# LED_Matrix.net
KiCad netlist of a schematic drawn in Altium Designer
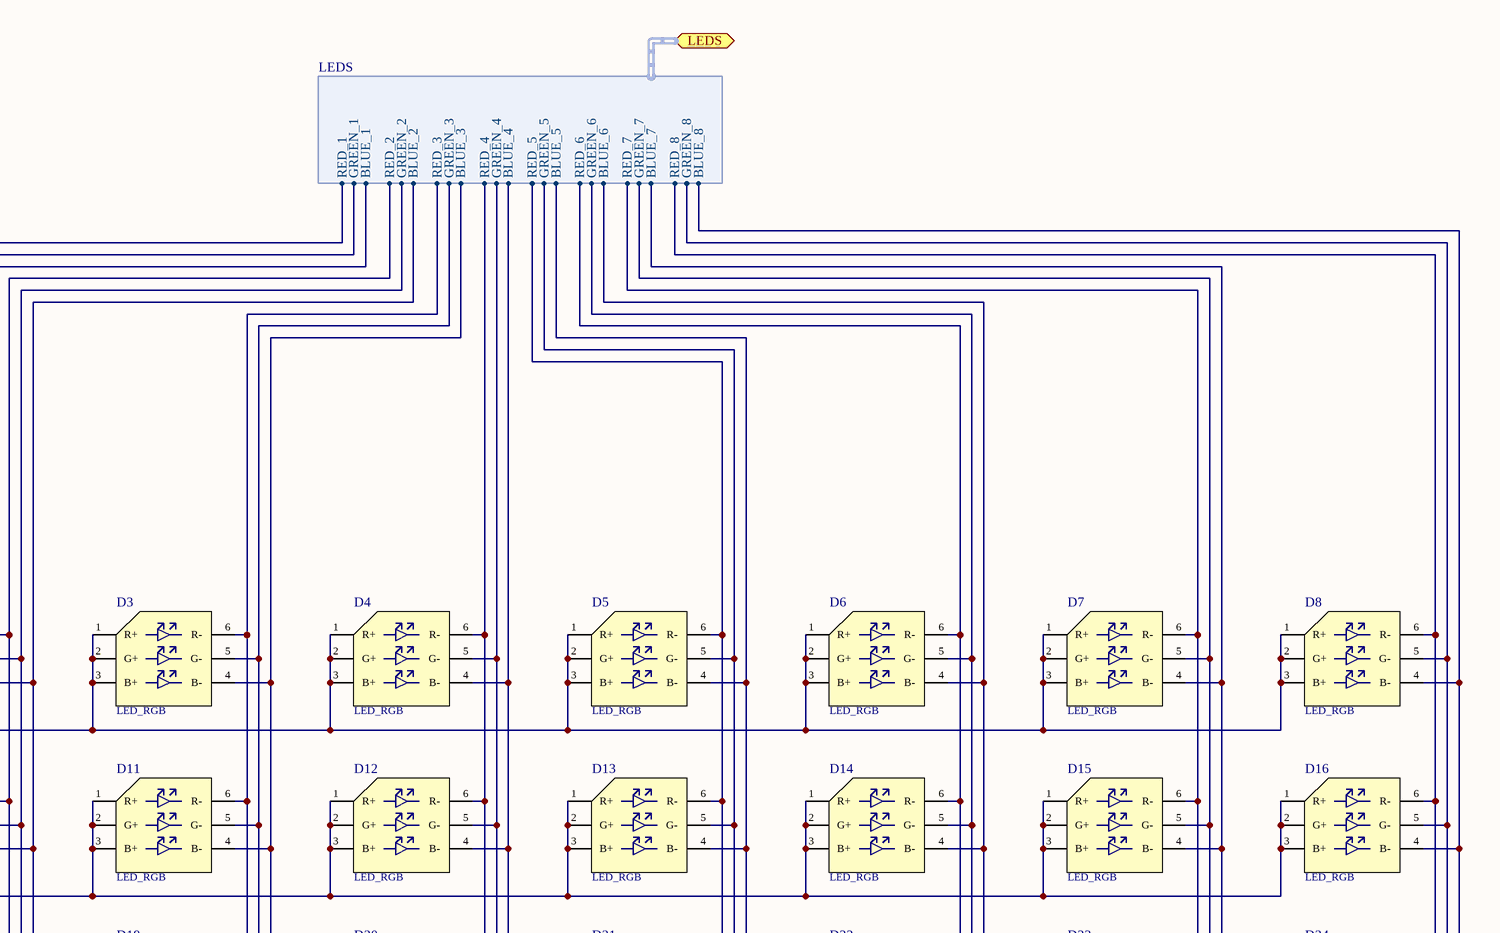
[diagram p0: LED Matrix.SchDoc, top right]
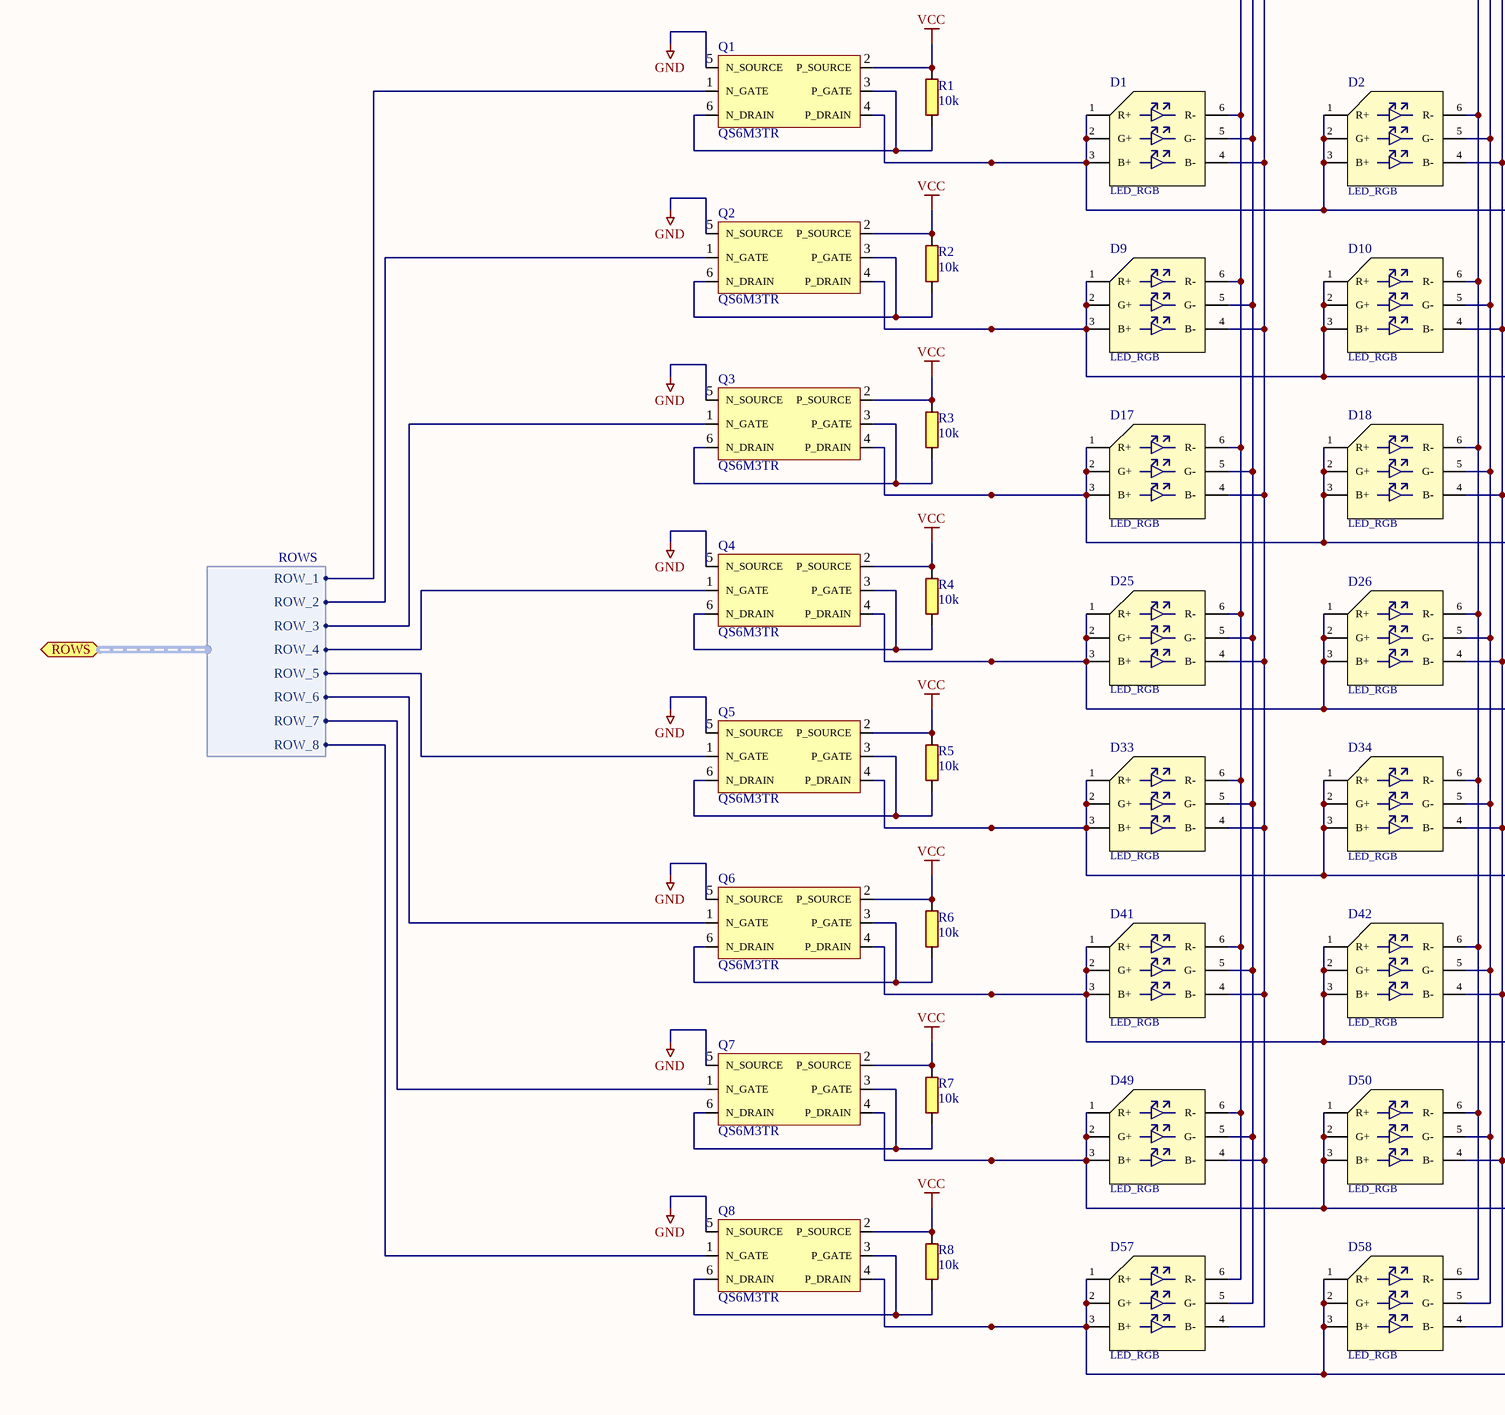
[diagram p1: LED Matrix.SchDoc, bottom left]
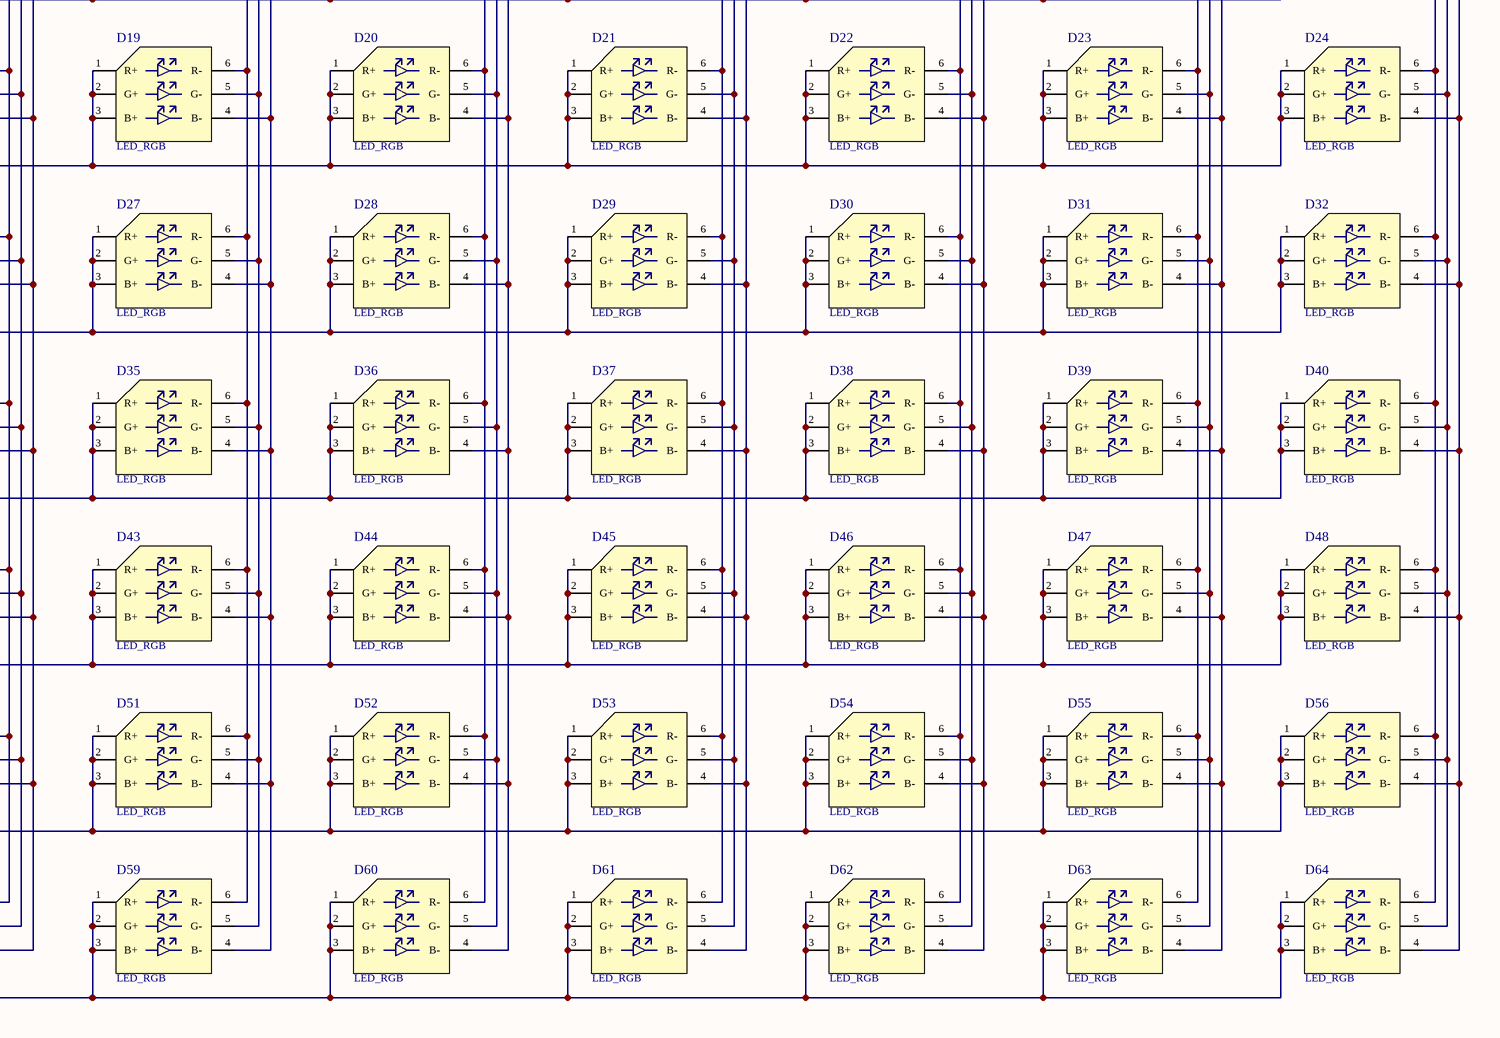
[diagram p2: LED Matrix.SchDoc, bottom right]

(export (version "E")
  (design (tool "Eeschema 10.0.6"))
  (components
    (comp (ref "D1")
      (value "LED_RGB")
      (footprint "LED5050_RGB_N")
      (description "LED RGB, independent colors")
      (libsource (lib "OVLib") (part "LED_RGB_IND_CHIP"))
    )
    (comp (ref "D2")
      (value "LED_RGB")
      (footprint "LED5050_RGB_N")
      (description "LED RGB, independent colors")
      (libsource (lib "OVLib") (part "LED_RGB_IND_CHIP"))
    )
    (comp (ref "D3")
      (value "LED_RGB")
      (footprint "LED5050_RGB_N")
      (description "LED RGB, independent colors")
      (libsource (lib "OVLib") (part "LED_RGB_IND_CHIP"))
    )
    (comp (ref "D4")
      (value "LED_RGB")
      (footprint "LED5050_RGB_N")
      (description "LED RGB, independent colors")
      (libsource (lib "OVLib") (part "LED_RGB_IND_CHIP"))
    )
    (comp (ref "D5")
      (value "LED_RGB")
      (footprint "LED5050_RGB_N")
      (description "LED RGB, independent colors")
      (libsource (lib "OVLib") (part "LED_RGB_IND_CHIP"))
    )
    (comp (ref "D6")
      (value "LED_RGB")
      (footprint "LED5050_RGB_N")
      (description "LED RGB, independent colors")
      (libsource (lib "OVLib") (part "LED_RGB_IND_CHIP"))
    )
    (comp (ref "D7")
      (value "LED_RGB")
      (footprint "LED5050_RGB_N")
      (description "LED RGB, independent colors")
      (libsource (lib "OVLib") (part "LED_RGB_IND_CHIP"))
    )
    (comp (ref "D8")
      (value "LED_RGB")
      (footprint "LED5050_RGB_N")
      (description "LED RGB, independent colors")
      (libsource (lib "OVLib") (part "LED_RGB_IND_CHIP"))
    )
    (comp (ref "D9")
      (value "LED_RGB")
      (footprint "LED5050_RGB_N")
      (description "LED RGB, independent colors")
      (libsource (lib "OVLib") (part "LED_RGB_IND_CHIP"))
    )
    (comp (ref "D10")
      (value "LED_RGB")
      (footprint "LED5050_RGB_N")
      (description "LED RGB, independent colors")
      (libsource (lib "OVLib") (part "LED_RGB_IND_CHIP"))
    )
    (comp (ref "D11")
      (value "LED_RGB")
      (footprint "LED5050_RGB_N")
      (description "LED RGB, independent colors")
      (libsource (lib "OVLib") (part "LED_RGB_IND_CHIP"))
    )
    (comp (ref "D12")
      (value "LED_RGB")
      (footprint "LED5050_RGB_N")
      (description "LED RGB, independent colors")
      (libsource (lib "OVLib") (part "LED_RGB_IND_CHIP"))
    )
    (comp (ref "D13")
      (value "LED_RGB")
      (footprint "LED5050_RGB_N")
      (description "LED RGB, independent colors")
      (libsource (lib "OVLib") (part "LED_RGB_IND_CHIP"))
    )
    (comp (ref "D14")
      (value "LED_RGB")
      (footprint "LED5050_RGB_N")
      (description "LED RGB, independent colors")
      (libsource (lib "OVLib") (part "LED_RGB_IND_CHIP"))
    )
    (comp (ref "D15")
      (value "LED_RGB")
      (footprint "LED5050_RGB_N")
      (description "LED RGB, independent colors")
      (libsource (lib "OVLib") (part "LED_RGB_IND_CHIP"))
    )
    (comp (ref "D16")
      (value "LED_RGB")
      (footprint "LED5050_RGB_N")
      (description "LED RGB, independent colors")
      (libsource (lib "OVLib") (part "LED_RGB_IND_CHIP"))
    )
    (comp (ref "D17")
      (value "LED_RGB")
      (footprint "LED5050_RGB_N")
      (description "LED RGB, independent colors")
      (libsource (lib "OVLib") (part "LED_RGB_IND_CHIP"))
    )
    (comp (ref "D18")
      (value "LED_RGB")
      (footprint "LED5050_RGB_N")
      (description "LED RGB, independent colors")
      (libsource (lib "OVLib") (part "LED_RGB_IND_CHIP"))
    )
    (comp (ref "D19")
      (value "LED_RGB")
      (footprint "LED5050_RGB_N")
      (description "LED RGB, independent colors")
      (libsource (lib "OVLib") (part "LED_RGB_IND_CHIP"))
    )
    (comp (ref "D20")
      (value "LED_RGB")
      (footprint "LED5050_RGB_N")
      (description "LED RGB, independent colors")
      (libsource (lib "OVLib") (part "LED_RGB_IND_CHIP"))
    )
    (comp (ref "D21")
      (value "LED_RGB")
      (footprint "LED5050_RGB_N")
      (description "LED RGB, independent colors")
      (libsource (lib "OVLib") (part "LED_RGB_IND_CHIP"))
    )
    (comp (ref "D22")
      (value "LED_RGB")
      (footprint "LED5050_RGB_N")
      (description "LED RGB, independent colors")
      (libsource (lib "OVLib") (part "LED_RGB_IND_CHIP"))
    )
    (comp (ref "D23")
      (value "LED_RGB")
      (footprint "LED5050_RGB_N")
      (description "LED RGB, independent colors")
      (libsource (lib "OVLib") (part "LED_RGB_IND_CHIP"))
    )
    (comp (ref "D24")
      (value "LED_RGB")
      (footprint "LED5050_RGB_N")
      (description "LED RGB, independent colors")
      (libsource (lib "OVLib") (part "LED_RGB_IND_CHIP"))
    )
    (comp (ref "D25")
      (value "LED_RGB")
      (footprint "LED5050_RGB_N")
      (description "LED RGB, independent colors")
      (libsource (lib "OVLib") (part "LED_RGB_IND_CHIP"))
    )
    (comp (ref "D26")
      (value "LED_RGB")
      (footprint "LED5050_RGB_N")
      (description "LED RGB, independent colors")
      (libsource (lib "OVLib") (part "LED_RGB_IND_CHIP"))
    )
    (comp (ref "D27")
      (value "LED_RGB")
      (footprint "LED5050_RGB_N")
      (description "LED RGB, independent colors")
      (libsource (lib "OVLib") (part "LED_RGB_IND_CHIP"))
    )
    (comp (ref "D28")
      (value "LED_RGB")
      (footprint "LED5050_RGB_N")
      (description "LED RGB, independent colors")
      (libsource (lib "OVLib") (part "LED_RGB_IND_CHIP"))
    )
    (comp (ref "D29")
      (value "LED_RGB")
      (footprint "LED5050_RGB_N")
      (description "LED RGB, independent colors")
      (libsource (lib "OVLib") (part "LED_RGB_IND_CHIP"))
    )
    (comp (ref "D30")
      (value "LED_RGB")
      (footprint "LED5050_RGB_N")
      (description "LED RGB, independent colors")
      (libsource (lib "OVLib") (part "LED_RGB_IND_CHIP"))
    )
    (comp (ref "D31")
      (value "LED_RGB")
      (footprint "LED5050_RGB_N")
      (description "LED RGB, independent colors")
      (libsource (lib "OVLib") (part "LED_RGB_IND_CHIP"))
    )
    (comp (ref "D32")
      (value "LED_RGB")
      (footprint "LED5050_RGB_N")
      (description "LED RGB, independent colors")
      (libsource (lib "OVLib") (part "LED_RGB_IND_CHIP"))
    )
    (comp (ref "D33")
      (value "LED_RGB")
      (footprint "LED5050_RGB_N")
      (description "LED RGB, independent colors")
      (libsource (lib "OVLib") (part "LED_RGB_IND_CHIP"))
    )
    (comp (ref "D34")
      (value "LED_RGB")
      (footprint "LED5050_RGB_N")
      (description "LED RGB, independent colors")
      (libsource (lib "OVLib") (part "LED_RGB_IND_CHIP"))
    )
    (comp (ref "D35")
      (value "LED_RGB")
      (footprint "LED5050_RGB_N")
      (description "LED RGB, independent colors")
      (libsource (lib "OVLib") (part "LED_RGB_IND_CHIP"))
    )
    (comp (ref "D36")
      (value "LED_RGB")
      (footprint "LED5050_RGB_N")
      (description "LED RGB, independent colors")
      (libsource (lib "OVLib") (part "LED_RGB_IND_CHIP"))
    )
    (comp (ref "D37")
      (value "LED_RGB")
      (footprint "LED5050_RGB_N")
      (description "LED RGB, independent colors")
      (libsource (lib "OVLib") (part "LED_RGB_IND_CHIP"))
    )
    (comp (ref "D38")
      (value "LED_RGB")
      (footprint "LED5050_RGB_N")
      (description "LED RGB, independent colors")
      (libsource (lib "OVLib") (part "LED_RGB_IND_CHIP"))
    )
    (comp (ref "D39")
      (value "LED_RGB")
      (footprint "LED5050_RGB_N")
      (description "LED RGB, independent colors")
      (libsource (lib "OVLib") (part "LED_RGB_IND_CHIP"))
    )
    (comp (ref "D40")
      (value "LED_RGB")
      (footprint "LED5050_RGB_N")
      (description "LED RGB, independent colors")
      (libsource (lib "OVLib") (part "LED_RGB_IND_CHIP"))
    )
    (comp (ref "D41")
      (value "LED_RGB")
      (footprint "LED5050_RGB_N")
      (description "LED RGB, independent colors")
      (libsource (lib "OVLib") (part "LED_RGB_IND_CHIP"))
    )
    (comp (ref "D42")
      (value "LED_RGB")
      (footprint "LED5050_RGB_N")
      (description "LED RGB, independent colors")
      (libsource (lib "OVLib") (part "LED_RGB_IND_CHIP"))
    )
    (comp (ref "D43")
      (value "LED_RGB")
      (footprint "LED5050_RGB_N")
      (description "LED RGB, independent colors")
      (libsource (lib "OVLib") (part "LED_RGB_IND_CHIP"))
    )
    (comp (ref "D44")
      (value "LED_RGB")
      (footprint "LED5050_RGB_N")
      (description "LED RGB, independent colors")
      (libsource (lib "OVLib") (part "LED_RGB_IND_CHIP"))
    )
    (comp (ref "D45")
      (value "LED_RGB")
      (footprint "LED5050_RGB_N")
      (description "LED RGB, independent colors")
      (libsource (lib "OVLib") (part "LED_RGB_IND_CHIP"))
    )
    (comp (ref "D46")
      (value "LED_RGB")
      (footprint "LED5050_RGB_N")
      (description "LED RGB, independent colors")
      (libsource (lib "OVLib") (part "LED_RGB_IND_CHIP"))
    )
    (comp (ref "D47")
      (value "LED_RGB")
      (footprint "LED5050_RGB_N")
      (description "LED RGB, independent colors")
      (libsource (lib "OVLib") (part "LED_RGB_IND_CHIP"))
    )
    (comp (ref "D48")
      (value "LED_RGB")
      (footprint "LED5050_RGB_N")
      (description "LED RGB, independent colors")
      (libsource (lib "OVLib") (part "LED_RGB_IND_CHIP"))
    )
    (comp (ref "D49")
      (value "LED_RGB")
      (footprint "LED5050_RGB_N")
      (description "LED RGB, independent colors")
      (libsource (lib "OVLib") (part "LED_RGB_IND_CHIP"))
    )
    (comp (ref "D50")
      (value "LED_RGB")
      (footprint "LED5050_RGB_N")
      (description "LED RGB, independent colors")
      (libsource (lib "OVLib") (part "LED_RGB_IND_CHIP"))
    )
    (comp (ref "D51")
      (value "LED_RGB")
      (footprint "LED5050_RGB_N")
      (description "LED RGB, independent colors")
      (libsource (lib "OVLib") (part "LED_RGB_IND_CHIP"))
    )
    (comp (ref "D52")
      (value "LED_RGB")
      (footprint "LED5050_RGB_N")
      (description "LED RGB, independent colors")
      (libsource (lib "OVLib") (part "LED_RGB_IND_CHIP"))
    )
    (comp (ref "D53")
      (value "LED_RGB")
      (footprint "LED5050_RGB_N")
      (description "LED RGB, independent colors")
      (libsource (lib "OVLib") (part "LED_RGB_IND_CHIP"))
    )
    (comp (ref "D54")
      (value "LED_RGB")
      (footprint "LED5050_RGB_N")
      (description "LED RGB, independent colors")
      (libsource (lib "OVLib") (part "LED_RGB_IND_CHIP"))
    )
    (comp (ref "D55")
      (value "LED_RGB")
      (footprint "LED5050_RGB_N")
      (description "LED RGB, independent colors")
      (libsource (lib "OVLib") (part "LED_RGB_IND_CHIP"))
    )
    (comp (ref "D56")
      (value "LED_RGB")
      (footprint "LED5050_RGB_N")
      (description "LED RGB, independent colors")
      (libsource (lib "OVLib") (part "LED_RGB_IND_CHIP"))
    )
    (comp (ref "D57")
      (value "LED_RGB")
      (footprint "LED5050_RGB_N")
      (description "LED RGB, independent colors")
      (libsource (lib "OVLib") (part "LED_RGB_IND_CHIP"))
    )
    (comp (ref "D58")
      (value "LED_RGB")
      (footprint "LED5050_RGB_N")
      (description "LED RGB, independent colors")
      (libsource (lib "OVLib") (part "LED_RGB_IND_CHIP"))
    )
    (comp (ref "D59")
      (value "LED_RGB")
      (footprint "LED5050_RGB_N")
      (description "LED RGB, independent colors")
      (libsource (lib "OVLib") (part "LED_RGB_IND_CHIP"))
    )
    (comp (ref "D60")
      (value "LED_RGB")
      (footprint "LED5050_RGB_N")
      (description "LED RGB, independent colors")
      (libsource (lib "OVLib") (part "LED_RGB_IND_CHIP"))
    )
    (comp (ref "D61")
      (value "LED_RGB")
      (footprint "LED5050_RGB_N")
      (description "LED RGB, independent colors")
      (libsource (lib "OVLib") (part "LED_RGB_IND_CHIP"))
    )
    (comp (ref "D62")
      (value "LED_RGB")
      (footprint "LED5050_RGB_N")
      (description "LED RGB, independent colors")
      (libsource (lib "OVLib") (part "LED_RGB_IND_CHIP"))
    )
    (comp (ref "D63")
      (value "LED_RGB")
      (footprint "LED5050_RGB_N")
      (description "LED RGB, independent colors")
      (libsource (lib "OVLib") (part "LED_RGB_IND_CHIP"))
    )
    (comp (ref "D64")
      (value "LED_RGB")
      (footprint "LED5050_RGB_N")
      (description "LED RGB, independent colors")
      (libsource (lib "OVLib") (part "LED_RGB_IND_CHIP"))
    )
    (comp (ref "Q1") (value "QS6M3TR") (footprint "QS6M3TR") (libsource (lib "Schlib1") (part "QS6M3TR")))
    (comp (ref "Q2") (value "QS6M3TR") (footprint "QS6M3TR") (libsource (lib "Schlib1") (part "QS6M3TR")))
    (comp (ref "Q3") (value "QS6M3TR") (footprint "QS6M3TR") (libsource (lib "Schlib1") (part "QS6M3TR")))
    (comp (ref "Q4") (value "QS6M3TR") (footprint "QS6M3TR") (libsource (lib "Schlib1") (part "QS6M3TR")))
    (comp (ref "Q5") (value "QS6M3TR") (footprint "QS6M3TR") (libsource (lib "Schlib1") (part "QS6M3TR")))
    (comp (ref "Q6") (value "QS6M3TR") (footprint "QS6M3TR") (libsource (lib "Schlib1") (part "QS6M3TR")))
    (comp (ref "Q7") (value "QS6M3TR") (footprint "QS6M3TR") (libsource (lib "Schlib1") (part "QS6M3TR")))
    (comp (ref "Q8") (value "QS6M3TR") (footprint "QS6M3TR") (libsource (lib "Schlib1") (part "QS6M3TR")))
    (comp (ref "R1")
      (value "10k")
      (footprint "RESC0603(1608)_N")
      (description "0.1W 1% Thick film resistor")
      (libsource (lib "OVLib") (part "Resistor2"))
    )
    (comp (ref "R2")
      (value "10k")
      (footprint "RESC0603(1608)_N")
      (description "0.1W 1% Thick film resistor")
      (libsource (lib "OVLib") (part "Resistor2"))
    )
    (comp (ref "R3")
      (value "10k")
      (footprint "RESC0603(1608)_N")
      (description "0.1W 1% Thick film resistor")
      (libsource (lib "OVLib") (part "Resistor2"))
    )
    (comp (ref "R4")
      (value "10k")
      (footprint "RESC0603(1608)_N")
      (description "0.1W 1% Thick film resistor")
      (libsource (lib "OVLib") (part "Resistor2"))
    )
    (comp (ref "R5")
      (value "10k")
      (footprint "RESC0603(1608)_N")
      (description "0.1W 1% Thick film resistor")
      (libsource (lib "OVLib") (part "Resistor2"))
    )
    (comp (ref "R6")
      (value "10k")
      (footprint "RESC0603(1608)_N")
      (description "0.1W 1% Thick film resistor")
      (libsource (lib "OVLib") (part "Resistor2"))
    )
    (comp (ref "R7")
      (value "10k")
      (footprint "RESC0603(1608)_N")
      (description "0.1W 1% Thick film resistor")
      (libsource (lib "OVLib") (part "Resistor2"))
    )
    (comp (ref "R8")
      (value "10k")
      (footprint "RESC0603(1608)_N")
      (description "0.1W 1% Thick film resistor")
      (libsource (lib "OVLib") (part "Resistor2"))
    )
  )
  (nets
    (net (code "3") (name "/BLUE_4") (class "Default")
      (node (ref "D12") (pin "4") (pinfunction "B-_4") (pintype "power_in"))
      (node (ref "D20") (pin "4") (pinfunction "B-_4") (pintype "power_in"))
      (node (ref "D28") (pin "4") (pinfunction "B-_4") (pintype "power_in"))
      (node (ref "D36") (pin "4") (pinfunction "B-_4") (pintype "power_in"))
      (node (ref "D4") (pin "4") (pinfunction "B-_4") (pintype "power_in"))
      (node (ref "D44") (pin "4") (pinfunction "B-_4") (pintype "power_in"))
      (node (ref "D52") (pin "4") (pinfunction "B-_4") (pintype "power_in"))
      (node (ref "D60") (pin "4") (pinfunction "B-_4") (pintype "power_in"))
    )
    (net (code "4") (name "/GREEN_4") (class "Default")
      (node (ref "D12") (pin "5") (pinfunction "G-_5") (pintype "power_in"))
      (node (ref "D20") (pin "5") (pinfunction "G-_5") (pintype "power_in"))
      (node (ref "D28") (pin "5") (pinfunction "G-_5") (pintype "power_in"))
      (node (ref "D36") (pin "5") (pinfunction "G-_5") (pintype "power_in"))
      (node (ref "D4") (pin "5") (pinfunction "G-_5") (pintype "power_in"))
      (node (ref "D44") (pin "5") (pinfunction "G-_5") (pintype "power_in"))
      (node (ref "D52") (pin "5") (pinfunction "G-_5") (pintype "power_in"))
      (node (ref "D60") (pin "5") (pinfunction "G-_5") (pintype "power_in"))
    )
    (net (code "7") (name "GND") (class "Default")
      (node (ref "Q1") (pin "5") (pinfunction "N_SOURCE_5") (pintype "passive"))
      (node (ref "Q2") (pin "5") (pinfunction "N_SOURCE_5") (pintype "passive"))
      (node (ref "Q3") (pin "5") (pinfunction "N_SOURCE_5") (pintype "passive"))
      (node (ref "Q4") (pin "5") (pinfunction "N_SOURCE_5") (pintype "passive"))
      (node (ref "Q5") (pin "5") (pinfunction "N_SOURCE_5") (pintype "passive"))
      (node (ref "Q6") (pin "5") (pinfunction "N_SOURCE_5") (pintype "passive"))
      (node (ref "Q7") (pin "5") (pinfunction "N_SOURCE_5") (pintype "passive"))
      (node (ref "Q8") (pin "5") (pinfunction "N_SOURCE_5") (pintype "passive"))
    )
    (net (code "8") (name "Net-(D1-B+)") (class "Default")
      (node (ref "D1") (pin "1") (pinfunction "R+_1") (pintype "power_in"))
      (node (ref "D1") (pin "2") (pinfunction "G+_2") (pintype "power_in"))
      (node (ref "D1") (pin "3") (pinfunction "B+_3") (pintype "power_in"))
      (node (ref "D2") (pin "1") (pinfunction "R+_1") (pintype "power_in"))
      (node (ref "D2") (pin "2") (pinfunction "G+_2") (pintype "power_in"))
      (node (ref "D2") (pin "3") (pinfunction "B+_3") (pintype "power_in"))
      (node (ref "D3") (pin "1") (pinfunction "R+_1") (pintype "power_in"))
      (node (ref "D3") (pin "2") (pinfunction "G+_2") (pintype "power_in"))
      (node (ref "D3") (pin "3") (pinfunction "B+_3") (pintype "power_in"))
      (node (ref "D4") (pin "1") (pinfunction "R+_1") (pintype "power_in"))
      (node (ref "D4") (pin "2") (pinfunction "G+_2") (pintype "power_in"))
      (node (ref "D4") (pin "3") (pinfunction "B+_3") (pintype "power_in"))
      (node (ref "D5") (pin "1") (pinfunction "R+_1") (pintype "power_in"))
      (node (ref "D5") (pin "2") (pinfunction "G+_2") (pintype "power_in"))
      (node (ref "D5") (pin "3") (pinfunction "B+_3") (pintype "power_in"))
      (node (ref "D6") (pin "1") (pinfunction "R+_1") (pintype "power_in"))
      (node (ref "D6") (pin "2") (pinfunction "G+_2") (pintype "power_in"))
      (node (ref "D6") (pin "3") (pinfunction "B+_3") (pintype "power_in"))
      (node (ref "D7") (pin "1") (pinfunction "R+_1") (pintype "power_in"))
      (node (ref "D7") (pin "2") (pinfunction "G+_2") (pintype "power_in"))
      (node (ref "D7") (pin "3") (pinfunction "B+_3") (pintype "power_in"))
      (node (ref "D8") (pin "1") (pinfunction "R+_1") (pintype "power_in"))
      (node (ref "D8") (pin "2") (pinfunction "G+_2") (pintype "power_in"))
      (node (ref "D8") (pin "3") (pinfunction "B+_3") (pintype "power_in"))
      (node (ref "Q1") (pin "4") (pinfunction "P_DRAIN_4") (pintype "passive"))
    )
    (net (code "9") (name "Net-(D1-B-)") (class "Default")
      (node (ref "D1") (pin "4") (pinfunction "B-_4") (pintype "power_in"))
      (node (ref "D17") (pin "4") (pinfunction "B-_4") (pintype "power_in"))
      (node (ref "D25") (pin "4") (pinfunction "B-_4") (pintype "power_in"))
      (node (ref "D33") (pin "4") (pinfunction "B-_4") (pintype "power_in"))
      (node (ref "D41") (pin "4") (pinfunction "B-_4") (pintype "power_in"))
      (node (ref "D49") (pin "4") (pinfunction "B-_4") (pintype "power_in"))
      (node (ref "D57") (pin "4") (pinfunction "B-_4") (pintype "power_in"))
      (node (ref "D9") (pin "4") (pinfunction "B-_4") (pintype "power_in"))
    )
    (net (code "10") (name "Net-(D1-G-)") (class "Default")
      (node (ref "D1") (pin "5") (pinfunction "G-_5") (pintype "power_in"))
      (node (ref "D17") (pin "5") (pinfunction "G-_5") (pintype "power_in"))
      (node (ref "D25") (pin "5") (pinfunction "G-_5") (pintype "power_in"))
      (node (ref "D33") (pin "5") (pinfunction "G-_5") (pintype "power_in"))
      (node (ref "D41") (pin "5") (pinfunction "G-_5") (pintype "power_in"))
      (node (ref "D49") (pin "5") (pinfunction "G-_5") (pintype "power_in"))
      (node (ref "D57") (pin "5") (pinfunction "G-_5") (pintype "power_in"))
      (node (ref "D9") (pin "5") (pinfunction "G-_5") (pintype "power_in"))
    )
    (net (code "11") (name "Net-(D1-R-)") (class "Default")
      (node (ref "D1") (pin "6") (pinfunction "R-_6") (pintype "power_in"))
      (node (ref "D17") (pin "6") (pinfunction "R-_6") (pintype "power_in"))
      (node (ref "D25") (pin "6") (pinfunction "R-_6") (pintype "power_in"))
      (node (ref "D33") (pin "6") (pinfunction "R-_6") (pintype "power_in"))
      (node (ref "D41") (pin "6") (pinfunction "R-_6") (pintype "power_in"))
      (node (ref "D49") (pin "6") (pinfunction "R-_6") (pintype "power_in"))
      (node (ref "D57") (pin "6") (pinfunction "R-_6") (pintype "power_in"))
      (node (ref "D9") (pin "6") (pinfunction "R-_6") (pintype "power_in"))
    )
    (net (code "12") (name "Net-(D10-B+)") (class "Default")
      (node (ref "D10") (pin "1") (pinfunction "R+_1") (pintype "power_in"))
      (node (ref "D10") (pin "2") (pinfunction "G+_2") (pintype "power_in"))
      (node (ref "D10") (pin "3") (pinfunction "B+_3") (pintype "power_in"))
      (node (ref "D11") (pin "1") (pinfunction "R+_1") (pintype "power_in"))
      (node (ref "D11") (pin "2") (pinfunction "G+_2") (pintype "power_in"))
      (node (ref "D11") (pin "3") (pinfunction "B+_3") (pintype "power_in"))
      (node (ref "D12") (pin "1") (pinfunction "R+_1") (pintype "power_in"))
      (node (ref "D12") (pin "2") (pinfunction "G+_2") (pintype "power_in"))
      (node (ref "D12") (pin "3") (pinfunction "B+_3") (pintype "power_in"))
      (node (ref "D13") (pin "1") (pinfunction "R+_1") (pintype "power_in"))
      (node (ref "D13") (pin "2") (pinfunction "G+_2") (pintype "power_in"))
      (node (ref "D13") (pin "3") (pinfunction "B+_3") (pintype "power_in"))
      (node (ref "D14") (pin "1") (pinfunction "R+_1") (pintype "power_in"))
      (node (ref "D14") (pin "2") (pinfunction "G+_2") (pintype "power_in"))
      (node (ref "D14") (pin "3") (pinfunction "B+_3") (pintype "power_in"))
      (node (ref "D15") (pin "1") (pinfunction "R+_1") (pintype "power_in"))
      (node (ref "D15") (pin "2") (pinfunction "G+_2") (pintype "power_in"))
      (node (ref "D15") (pin "3") (pinfunction "B+_3") (pintype "power_in"))
      (node (ref "D16") (pin "1") (pinfunction "R+_1") (pintype "power_in"))
      (node (ref "D16") (pin "2") (pinfunction "G+_2") (pintype "power_in"))
      (node (ref "D16") (pin "3") (pinfunction "B+_3") (pintype "power_in"))
      (node (ref "D9") (pin "1") (pinfunction "R+_1") (pintype "power_in"))
      (node (ref "D9") (pin "2") (pinfunction "G+_2") (pintype "power_in"))
      (node (ref "D9") (pin "3") (pinfunction "B+_3") (pintype "power_in"))
      (node (ref "Q2") (pin "4") (pinfunction "P_DRAIN_4") (pintype "passive"))
    )
    (net (code "13") (name "Net-(D10-B-)") (class "Default")
      (node (ref "D10") (pin "4") (pinfunction "B-_4") (pintype "power_in"))
      (node (ref "D18") (pin "4") (pinfunction "B-_4") (pintype "power_in"))
      (node (ref "D2") (pin "4") (pinfunction "B-_4") (pintype "power_in"))
      (node (ref "D26") (pin "4") (pinfunction "B-_4") (pintype "power_in"))
      (node (ref "D34") (pin "4") (pinfunction "B-_4") (pintype "power_in"))
      (node (ref "D42") (pin "4") (pinfunction "B-_4") (pintype "power_in"))
      (node (ref "D50") (pin "4") (pinfunction "B-_4") (pintype "power_in"))
      (node (ref "D58") (pin "4") (pinfunction "B-_4") (pintype "power_in"))
    )
    (net (code "14") (name "Net-(D10-G-)") (class "Default")
      (node (ref "D10") (pin "5") (pinfunction "G-_5") (pintype "power_in"))
      (node (ref "D18") (pin "5") (pinfunction "G-_5") (pintype "power_in"))
      (node (ref "D2") (pin "5") (pinfunction "G-_5") (pintype "power_in"))
      (node (ref "D26") (pin "5") (pinfunction "G-_5") (pintype "power_in"))
      (node (ref "D34") (pin "5") (pinfunction "G-_5") (pintype "power_in"))
      (node (ref "D42") (pin "5") (pinfunction "G-_5") (pintype "power_in"))
      (node (ref "D50") (pin "5") (pinfunction "G-_5") (pintype "power_in"))
      (node (ref "D58") (pin "5") (pinfunction "G-_5") (pintype "power_in"))
    )
    (net (code "15") (name "Net-(D10-R-)") (class "Default")
      (node (ref "D10") (pin "6") (pinfunction "R-_6") (pintype "power_in"))
      (node (ref "D18") (pin "6") (pinfunction "R-_6") (pintype "power_in"))
      (node (ref "D2") (pin "6") (pinfunction "R-_6") (pintype "power_in"))
      (node (ref "D26") (pin "6") (pinfunction "R-_6") (pintype "power_in"))
      (node (ref "D34") (pin "6") (pinfunction "R-_6") (pintype "power_in"))
      (node (ref "D42") (pin "6") (pinfunction "R-_6") (pintype "power_in"))
      (node (ref "D50") (pin "6") (pinfunction "R-_6") (pintype "power_in"))
      (node (ref "D58") (pin "6") (pinfunction "R-_6") (pintype "power_in"))
    )
    (net (code "16") (name "Net-(D11-B-)") (class "Default")
      (node (ref "D11") (pin "4") (pinfunction "B-_4") (pintype "power_in"))
      (node (ref "D19") (pin "4") (pinfunction "B-_4") (pintype "power_in"))
      (node (ref "D27") (pin "4") (pinfunction "B-_4") (pintype "power_in"))
      (node (ref "D3") (pin "4") (pinfunction "B-_4") (pintype "power_in"))
      (node (ref "D35") (pin "4") (pinfunction "B-_4") (pintype "power_in"))
      (node (ref "D43") (pin "4") (pinfunction "B-_4") (pintype "power_in"))
      (node (ref "D51") (pin "4") (pinfunction "B-_4") (pintype "power_in"))
      (node (ref "D59") (pin "4") (pinfunction "B-_4") (pintype "power_in"))
    )
    (net (code "17") (name "Net-(D11-G-)") (class "Default")
      (node (ref "D11") (pin "5") (pinfunction "G-_5") (pintype "power_in"))
      (node (ref "D19") (pin "5") (pinfunction "G-_5") (pintype "power_in"))
      (node (ref "D27") (pin "5") (pinfunction "G-_5") (pintype "power_in"))
      (node (ref "D3") (pin "5") (pinfunction "G-_5") (pintype "power_in"))
      (node (ref "D35") (pin "5") (pinfunction "G-_5") (pintype "power_in"))
      (node (ref "D43") (pin "5") (pinfunction "G-_5") (pintype "power_in"))
      (node (ref "D51") (pin "5") (pinfunction "G-_5") (pintype "power_in"))
      (node (ref "D59") (pin "5") (pinfunction "G-_5") (pintype "power_in"))
    )
    (net (code "18") (name "Net-(D11-R-)") (class "Default")
      (node (ref "D11") (pin "6") (pinfunction "R-_6") (pintype "power_in"))
      (node (ref "D19") (pin "6") (pinfunction "R-_6") (pintype "power_in"))
      (node (ref "D27") (pin "6") (pinfunction "R-_6") (pintype "power_in"))
      (node (ref "D3") (pin "6") (pinfunction "R-_6") (pintype "power_in"))
      (node (ref "D35") (pin "6") (pinfunction "R-_6") (pintype "power_in"))
      (node (ref "D43") (pin "6") (pinfunction "R-_6") (pintype "power_in"))
      (node (ref "D51") (pin "6") (pinfunction "R-_6") (pintype "power_in"))
      (node (ref "D59") (pin "6") (pinfunction "R-_6") (pintype "power_in"))
    )
    (net (code "19") (name "Net-(D12-R-)") (class "Default")
      (node (ref "D12") (pin "6") (pinfunction "R-_6") (pintype "power_in"))
      (node (ref "D20") (pin "6") (pinfunction "R-_6") (pintype "power_in"))
      (node (ref "D28") (pin "6") (pinfunction "R-_6") (pintype "power_in"))
      (node (ref "D36") (pin "6") (pinfunction "R-_6") (pintype "power_in"))
      (node (ref "D4") (pin "6") (pinfunction "R-_6") (pintype "power_in"))
      (node (ref "D44") (pin "6") (pinfunction "R-_6") (pintype "power_in"))
      (node (ref "D52") (pin "6") (pinfunction "R-_6") (pintype "power_in"))
      (node (ref "D60") (pin "6") (pinfunction "R-_6") (pintype "power_in"))
    )
    (net (code "20") (name "Net-(D13-B-)") (class "Default")
      (node (ref "D13") (pin "4") (pinfunction "B-_4") (pintype "power_in"))
      (node (ref "D21") (pin "4") (pinfunction "B-_4") (pintype "power_in"))
      (node (ref "D29") (pin "4") (pinfunction "B-_4") (pintype "power_in"))
      (node (ref "D37") (pin "4") (pinfunction "B-_4") (pintype "power_in"))
      (node (ref "D45") (pin "4") (pinfunction "B-_4") (pintype "power_in"))
      (node (ref "D5") (pin "4") (pinfunction "B-_4") (pintype "power_in"))
      (node (ref "D53") (pin "4") (pinfunction "B-_4") (pintype "power_in"))
      (node (ref "D61") (pin "4") (pinfunction "B-_4") (pintype "power_in"))
    )
    (net (code "21") (name "Net-(D13-G-)") (class "Default")
      (node (ref "D13") (pin "5") (pinfunction "G-_5") (pintype "power_in"))
      (node (ref "D21") (pin "5") (pinfunction "G-_5") (pintype "power_in"))
      (node (ref "D29") (pin "5") (pinfunction "G-_5") (pintype "power_in"))
      (node (ref "D37") (pin "5") (pinfunction "G-_5") (pintype "power_in"))
      (node (ref "D45") (pin "5") (pinfunction "G-_5") (pintype "power_in"))
      (node (ref "D5") (pin "5") (pinfunction "G-_5") (pintype "power_in"))
      (node (ref "D53") (pin "5") (pinfunction "G-_5") (pintype "power_in"))
      (node (ref "D61") (pin "5") (pinfunction "G-_5") (pintype "power_in"))
    )
    (net (code "22") (name "Net-(D13-R-)") (class "Default")
      (node (ref "D13") (pin "6") (pinfunction "R-_6") (pintype "power_in"))
      (node (ref "D21") (pin "6") (pinfunction "R-_6") (pintype "power_in"))
      (node (ref "D29") (pin "6") (pinfunction "R-_6") (pintype "power_in"))
      (node (ref "D37") (pin "6") (pinfunction "R-_6") (pintype "power_in"))
      (node (ref "D45") (pin "6") (pinfunction "R-_6") (pintype "power_in"))
      (node (ref "D5") (pin "6") (pinfunction "R-_6") (pintype "power_in"))
      (node (ref "D53") (pin "6") (pinfunction "R-_6") (pintype "power_in"))
      (node (ref "D61") (pin "6") (pinfunction "R-_6") (pintype "power_in"))
    )
    (net (code "23") (name "Net-(D14-B-)") (class "Default")
      (node (ref "D14") (pin "4") (pinfunction "B-_4") (pintype "power_in"))
      (node (ref "D22") (pin "4") (pinfunction "B-_4") (pintype "power_in"))
      (node (ref "D30") (pin "4") (pinfunction "B-_4") (pintype "power_in"))
      (node (ref "D38") (pin "4") (pinfunction "B-_4") (pintype "power_in"))
      (node (ref "D46") (pin "4") (pinfunction "B-_4") (pintype "power_in"))
      (node (ref "D54") (pin "4") (pinfunction "B-_4") (pintype "power_in"))
      (node (ref "D6") (pin "4") (pinfunction "B-_4") (pintype "power_in"))
      (node (ref "D62") (pin "4") (pinfunction "B-_4") (pintype "power_in"))
    )
    (net (code "24") (name "Net-(D14-G-)") (class "Default")
      (node (ref "D14") (pin "5") (pinfunction "G-_5") (pintype "power_in"))
      (node (ref "D22") (pin "5") (pinfunction "G-_5") (pintype "power_in"))
      (node (ref "D30") (pin "5") (pinfunction "G-_5") (pintype "power_in"))
      (node (ref "D38") (pin "5") (pinfunction "G-_5") (pintype "power_in"))
      (node (ref "D46") (pin "5") (pinfunction "G-_5") (pintype "power_in"))
      (node (ref "D54") (pin "5") (pinfunction "G-_5") (pintype "power_in"))
      (node (ref "D6") (pin "5") (pinfunction "G-_5") (pintype "power_in"))
      (node (ref "D62") (pin "5") (pinfunction "G-_5") (pintype "power_in"))
    )
    (net (code "25") (name "Net-(D14-R-)") (class "Default")
      (node (ref "D14") (pin "6") (pinfunction "R-_6") (pintype "power_in"))
      (node (ref "D22") (pin "6") (pinfunction "R-_6") (pintype "power_in"))
      (node (ref "D30") (pin "6") (pinfunction "R-_6") (pintype "power_in"))
      (node (ref "D38") (pin "6") (pinfunction "R-_6") (pintype "power_in"))
      (node (ref "D46") (pin "6") (pinfunction "R-_6") (pintype "power_in"))
      (node (ref "D54") (pin "6") (pinfunction "R-_6") (pintype "power_in"))
      (node (ref "D6") (pin "6") (pinfunction "R-_6") (pintype "power_in"))
      (node (ref "D62") (pin "6") (pinfunction "R-_6") (pintype "power_in"))
    )
    (net (code "26") (name "Net-(D15-B-)") (class "Default")
      (node (ref "D15") (pin "4") (pinfunction "B-_4") (pintype "power_in"))
      (node (ref "D23") (pin "4") (pinfunction "B-_4") (pintype "power_in"))
      (node (ref "D31") (pin "4") (pinfunction "B-_4") (pintype "power_in"))
      (node (ref "D39") (pin "4") (pinfunction "B-_4") (pintype "power_in"))
      (node (ref "D47") (pin "4") (pinfunction "B-_4") (pintype "power_in"))
      (node (ref "D55") (pin "4") (pinfunction "B-_4") (pintype "power_in"))
      (node (ref "D63") (pin "4") (pinfunction "B-_4") (pintype "power_in"))
      (node (ref "D7") (pin "4") (pinfunction "B-_4") (pintype "power_in"))
    )
    (net (code "27") (name "Net-(D15-G-)") (class "Default")
      (node (ref "D15") (pin "5") (pinfunction "G-_5") (pintype "power_in"))
      (node (ref "D23") (pin "5") (pinfunction "G-_5") (pintype "power_in"))
      (node (ref "D31") (pin "5") (pinfunction "G-_5") (pintype "power_in"))
      (node (ref "D39") (pin "5") (pinfunction "G-_5") (pintype "power_in"))
      (node (ref "D47") (pin "5") (pinfunction "G-_5") (pintype "power_in"))
      (node (ref "D55") (pin "5") (pinfunction "G-_5") (pintype "power_in"))
      (node (ref "D63") (pin "5") (pinfunction "G-_5") (pintype "power_in"))
      (node (ref "D7") (pin "5") (pinfunction "G-_5") (pintype "power_in"))
    )
    (net (code "28") (name "Net-(D15-R-)") (class "Default")
      (node (ref "D15") (pin "6") (pinfunction "R-_6") (pintype "power_in"))
      (node (ref "D23") (pin "6") (pinfunction "R-_6") (pintype "power_in"))
      (node (ref "D31") (pin "6") (pinfunction "R-_6") (pintype "power_in"))
      (node (ref "D39") (pin "6") (pinfunction "R-_6") (pintype "power_in"))
      (node (ref "D47") (pin "6") (pinfunction "R-_6") (pintype "power_in"))
      (node (ref "D55") (pin "6") (pinfunction "R-_6") (pintype "power_in"))
      (node (ref "D63") (pin "6") (pinfunction "R-_6") (pintype "power_in"))
      (node (ref "D7") (pin "6") (pinfunction "R-_6") (pintype "power_in"))
    )
    (net (code "29") (name "Net-(D16-B-)") (class "Default")
      (node (ref "D16") (pin "4") (pinfunction "B-_4") (pintype "power_in"))
      (node (ref "D24") (pin "4") (pinfunction "B-_4") (pintype "power_in"))
      (node (ref "D32") (pin "4") (pinfunction "B-_4") (pintype "power_in"))
      (node (ref "D40") (pin "4") (pinfunction "B-_4") (pintype "power_in"))
      (node (ref "D48") (pin "4") (pinfunction "B-_4") (pintype "power_in"))
      (node (ref "D56") (pin "4") (pinfunction "B-_4") (pintype "power_in"))
      (node (ref "D64") (pin "4") (pinfunction "B-_4") (pintype "power_in"))
      (node (ref "D8") (pin "4") (pinfunction "B-_4") (pintype "power_in"))
    )
    (net (code "30") (name "Net-(D16-G-)") (class "Default")
      (node (ref "D16") (pin "5") (pinfunction "G-_5") (pintype "power_in"))
      (node (ref "D24") (pin "5") (pinfunction "G-_5") (pintype "power_in"))
      (node (ref "D32") (pin "5") (pinfunction "G-_5") (pintype "power_in"))
      (node (ref "D40") (pin "5") (pinfunction "G-_5") (pintype "power_in"))
      (node (ref "D48") (pin "5") (pinfunction "G-_5") (pintype "power_in"))
      (node (ref "D56") (pin "5") (pinfunction "G-_5") (pintype "power_in"))
      (node (ref "D64") (pin "5") (pinfunction "G-_5") (pintype "power_in"))
      (node (ref "D8") (pin "5") (pinfunction "G-_5") (pintype "power_in"))
    )
    (net (code "31") (name "Net-(D16-R-)") (class "Default")
      (node (ref "D16") (pin "6") (pinfunction "R-_6") (pintype "power_in"))
      (node (ref "D24") (pin "6") (pinfunction "R-_6") (pintype "power_in"))
      (node (ref "D32") (pin "6") (pinfunction "R-_6") (pintype "power_in"))
      (node (ref "D40") (pin "6") (pinfunction "R-_6") (pintype "power_in"))
      (node (ref "D48") (pin "6") (pinfunction "R-_6") (pintype "power_in"))
      (node (ref "D56") (pin "6") (pinfunction "R-_6") (pintype "power_in"))
      (node (ref "D64") (pin "6") (pinfunction "R-_6") (pintype "power_in"))
      (node (ref "D8") (pin "6") (pinfunction "R-_6") (pintype "power_in"))
    )
    (net (code "32") (name "Net-(D17-B+)") (class "Default")
      (node (ref "D17") (pin "1") (pinfunction "R+_1") (pintype "power_in"))
      (node (ref "D17") (pin "2") (pinfunction "G+_2") (pintype "power_in"))
      (node (ref "D17") (pin "3") (pinfunction "B+_3") (pintype "power_in"))
      (node (ref "D18") (pin "1") (pinfunction "R+_1") (pintype "power_in"))
      (node (ref "D18") (pin "2") (pinfunction "G+_2") (pintype "power_in"))
      (node (ref "D18") (pin "3") (pinfunction "B+_3") (pintype "power_in"))
      (node (ref "D19") (pin "1") (pinfunction "R+_1") (pintype "power_in"))
      (node (ref "D19") (pin "2") (pinfunction "G+_2") (pintype "power_in"))
      (node (ref "D19") (pin "3") (pinfunction "B+_3") (pintype "power_in"))
      (node (ref "D20") (pin "1") (pinfunction "R+_1") (pintype "power_in"))
      (node (ref "D20") (pin "2") (pinfunction "G+_2") (pintype "power_in"))
      (node (ref "D20") (pin "3") (pinfunction "B+_3") (pintype "power_in"))
      (node (ref "D21") (pin "1") (pinfunction "R+_1") (pintype "power_in"))
      (node (ref "D21") (pin "2") (pinfunction "G+_2") (pintype "power_in"))
      (node (ref "D21") (pin "3") (pinfunction "B+_3") (pintype "power_in"))
      (node (ref "D22") (pin "1") (pinfunction "R+_1") (pintype "power_in"))
      (node (ref "D22") (pin "2") (pinfunction "G+_2") (pintype "power_in"))
      (node (ref "D22") (pin "3") (pinfunction "B+_3") (pintype "power_in"))
      (node (ref "D23") (pin "1") (pinfunction "R+_1") (pintype "power_in"))
      (node (ref "D23") (pin "2") (pinfunction "G+_2") (pintype "power_in"))
      (node (ref "D23") (pin "3") (pinfunction "B+_3") (pintype "power_in"))
      (node (ref "D24") (pin "1") (pinfunction "R+_1") (pintype "power_in"))
      (node (ref "D24") (pin "2") (pinfunction "G+_2") (pintype "power_in"))
      (node (ref "D24") (pin "3") (pinfunction "B+_3") (pintype "power_in"))
      (node (ref "Q3") (pin "4") (pinfunction "P_DRAIN_4") (pintype "passive"))
    )
    (net (code "33") (name "Net-(D25-B+)") (class "Default")
      (node (ref "D25") (pin "1") (pinfunction "R+_1") (pintype "power_in"))
      (node (ref "D25") (pin "2") (pinfunction "G+_2") (pintype "power_in"))
      (node (ref "D25") (pin "3") (pinfunction "B+_3") (pintype "power_in"))
      (node (ref "D26") (pin "1") (pinfunction "R+_1") (pintype "power_in"))
      (node (ref "D26") (pin "2") (pinfunction "G+_2") (pintype "power_in"))
      (node (ref "D26") (pin "3") (pinfunction "B+_3") (pintype "power_in"))
      (node (ref "D27") (pin "1") (pinfunction "R+_1") (pintype "power_in"))
      (node (ref "D27") (pin "2") (pinfunction "G+_2") (pintype "power_in"))
      (node (ref "D27") (pin "3") (pinfunction "B+_3") (pintype "power_in"))
      (node (ref "D28") (pin "1") (pinfunction "R+_1") (pintype "power_in"))
      (node (ref "D28") (pin "2") (pinfunction "G+_2") (pintype "power_in"))
      (node (ref "D28") (pin "3") (pinfunction "B+_3") (pintype "power_in"))
      (node (ref "D29") (pin "1") (pinfunction "R+_1") (pintype "power_in"))
      (node (ref "D29") (pin "2") (pinfunction "G+_2") (pintype "power_in"))
      (node (ref "D29") (pin "3") (pinfunction "B+_3") (pintype "power_in"))
      (node (ref "D30") (pin "1") (pinfunction "R+_1") (pintype "power_in"))
      (node (ref "D30") (pin "2") (pinfunction "G+_2") (pintype "power_in"))
      (node (ref "D30") (pin "3") (pinfunction "B+_3") (pintype "power_in"))
      (node (ref "D31") (pin "1") (pinfunction "R+_1") (pintype "power_in"))
      (node (ref "D31") (pin "2") (pinfunction "G+_2") (pintype "power_in"))
      (node (ref "D31") (pin "3") (pinfunction "B+_3") (pintype "power_in"))
      (node (ref "D32") (pin "1") (pinfunction "R+_1") (pintype "power_in"))
      (node (ref "D32") (pin "2") (pinfunction "G+_2") (pintype "power_in"))
      (node (ref "D32") (pin "3") (pinfunction "B+_3") (pintype "power_in"))
      (node (ref "Q4") (pin "4") (pinfunction "P_DRAIN_4") (pintype "passive"))
    )
    (net (code "34") (name "Net-(D33-B+)") (class "Default")
      (node (ref "D33") (pin "1") (pinfunction "R+_1") (pintype "power_in"))
      (node (ref "D33") (pin "2") (pinfunction "G+_2") (pintype "power_in"))
      (node (ref "D33") (pin "3") (pinfunction "B+_3") (pintype "power_in"))
      (node (ref "D34") (pin "1") (pinfunction "R+_1") (pintype "power_in"))
      (node (ref "D34") (pin "2") (pinfunction "G+_2") (pintype "power_in"))
      (node (ref "D34") (pin "3") (pinfunction "B+_3") (pintype "power_in"))
      (node (ref "D35") (pin "1") (pinfunction "R+_1") (pintype "power_in"))
      (node (ref "D35") (pin "2") (pinfunction "G+_2") (pintype "power_in"))
      (node (ref "D35") (pin "3") (pinfunction "B+_3") (pintype "power_in"))
      (node (ref "D36") (pin "1") (pinfunction "R+_1") (pintype "power_in"))
      (node (ref "D36") (pin "2") (pinfunction "G+_2") (pintype "power_in"))
      (node (ref "D36") (pin "3") (pinfunction "B+_3") (pintype "power_in"))
      (node (ref "D37") (pin "1") (pinfunction "R+_1") (pintype "power_in"))
      (node (ref "D37") (pin "2") (pinfunction "G+_2") (pintype "power_in"))
      (node (ref "D37") (pin "3") (pinfunction "B+_3") (pintype "power_in"))
      (node (ref "D38") (pin "1") (pinfunction "R+_1") (pintype "power_in"))
      (node (ref "D38") (pin "2") (pinfunction "G+_2") (pintype "power_in"))
      (node (ref "D38") (pin "3") (pinfunction "B+_3") (pintype "power_in"))
      (node (ref "D39") (pin "1") (pinfunction "R+_1") (pintype "power_in"))
      (node (ref "D39") (pin "2") (pinfunction "G+_2") (pintype "power_in"))
      (node (ref "D39") (pin "3") (pinfunction "B+_3") (pintype "power_in"))
      (node (ref "D40") (pin "1") (pinfunction "R+_1") (pintype "power_in"))
      (node (ref "D40") (pin "2") (pinfunction "G+_2") (pintype "power_in"))
      (node (ref "D40") (pin "3") (pinfunction "B+_3") (pintype "power_in"))
      (node (ref "Q5") (pin "4") (pinfunction "P_DRAIN_4") (pintype "passive"))
    )
    (net (code "35") (name "Net-(D41-B+)") (class "Default")
      (node (ref "D41") (pin "1") (pinfunction "R+_1") (pintype "power_in"))
      (node (ref "D41") (pin "2") (pinfunction "G+_2") (pintype "power_in"))
      (node (ref "D41") (pin "3") (pinfunction "B+_3") (pintype "power_in"))
      (node (ref "D42") (pin "1") (pinfunction "R+_1") (pintype "power_in"))
      (node (ref "D42") (pin "2") (pinfunction "G+_2") (pintype "power_in"))
      (node (ref "D42") (pin "3") (pinfunction "B+_3") (pintype "power_in"))
      (node (ref "D43") (pin "1") (pinfunction "R+_1") (pintype "power_in"))
      (node (ref "D43") (pin "2") (pinfunction "G+_2") (pintype "power_in"))
      (node (ref "D43") (pin "3") (pinfunction "B+_3") (pintype "power_in"))
      (node (ref "D44") (pin "1") (pinfunction "R+_1") (pintype "power_in"))
      (node (ref "D44") (pin "2") (pinfunction "G+_2") (pintype "power_in"))
      (node (ref "D44") (pin "3") (pinfunction "B+_3") (pintype "power_in"))
      (node (ref "D45") (pin "1") (pinfunction "R+_1") (pintype "power_in"))
      (node (ref "D45") (pin "2") (pinfunction "G+_2") (pintype "power_in"))
      (node (ref "D45") (pin "3") (pinfunction "B+_3") (pintype "power_in"))
      (node (ref "D46") (pin "1") (pinfunction "R+_1") (pintype "power_in"))
      (node (ref "D46") (pin "2") (pinfunction "G+_2") (pintype "power_in"))
      (node (ref "D46") (pin "3") (pinfunction "B+_3") (pintype "power_in"))
      (node (ref "D47") (pin "1") (pinfunction "R+_1") (pintype "power_in"))
      (node (ref "D47") (pin "2") (pinfunction "G+_2") (pintype "power_in"))
      (node (ref "D47") (pin "3") (pinfunction "B+_3") (pintype "power_in"))
      (node (ref "D48") (pin "1") (pinfunction "R+_1") (pintype "power_in"))
      (node (ref "D48") (pin "2") (pinfunction "G+_2") (pintype "power_in"))
      (node (ref "D48") (pin "3") (pinfunction "B+_3") (pintype "power_in"))
      (node (ref "Q6") (pin "4") (pinfunction "P_DRAIN_4") (pintype "passive"))
    )
    (net (code "36") (name "Net-(D49-B+)") (class "Default")
      (node (ref "D49") (pin "1") (pinfunction "R+_1") (pintype "power_in"))
      (node (ref "D49") (pin "2") (pinfunction "G+_2") (pintype "power_in"))
      (node (ref "D49") (pin "3") (pinfunction "B+_3") (pintype "power_in"))
      (node (ref "D50") (pin "1") (pinfunction "R+_1") (pintype "power_in"))
      (node (ref "D50") (pin "2") (pinfunction "G+_2") (pintype "power_in"))
      (node (ref "D50") (pin "3") (pinfunction "B+_3") (pintype "power_in"))
      (node (ref "D51") (pin "1") (pinfunction "R+_1") (pintype "power_in"))
      (node (ref "D51") (pin "2") (pinfunction "G+_2") (pintype "power_in"))
      (node (ref "D51") (pin "3") (pinfunction "B+_3") (pintype "power_in"))
      (node (ref "D52") (pin "1") (pinfunction "R+_1") (pintype "power_in"))
      (node (ref "D52") (pin "2") (pinfunction "G+_2") (pintype "power_in"))
      (node (ref "D52") (pin "3") (pinfunction "B+_3") (pintype "power_in"))
      (node (ref "D53") (pin "1") (pinfunction "R+_1") (pintype "power_in"))
      (node (ref "D53") (pin "2") (pinfunction "G+_2") (pintype "power_in"))
      (node (ref "D53") (pin "3") (pinfunction "B+_3") (pintype "power_in"))
      (node (ref "D54") (pin "1") (pinfunction "R+_1") (pintype "power_in"))
      (node (ref "D54") (pin "2") (pinfunction "G+_2") (pintype "power_in"))
      (node (ref "D54") (pin "3") (pinfunction "B+_3") (pintype "power_in"))
      (node (ref "D55") (pin "1") (pinfunction "R+_1") (pintype "power_in"))
      (node (ref "D55") (pin "2") (pinfunction "G+_2") (pintype "power_in"))
      (node (ref "D55") (pin "3") (pinfunction "B+_3") (pintype "power_in"))
      (node (ref "D56") (pin "1") (pinfunction "R+_1") (pintype "power_in"))
      (node (ref "D56") (pin "2") (pinfunction "G+_2") (pintype "power_in"))
      (node (ref "D56") (pin "3") (pinfunction "B+_3") (pintype "power_in"))
      (node (ref "Q7") (pin "4") (pinfunction "P_DRAIN_4") (pintype "passive"))
    )
    (net (code "37") (name "Net-(D57-B+)") (class "Default")
      (node (ref "D57") (pin "1") (pinfunction "R+_1") (pintype "power_in"))
      (node (ref "D57") (pin "2") (pinfunction "G+_2") (pintype "power_in"))
      (node (ref "D57") (pin "3") (pinfunction "B+_3") (pintype "power_in"))
      (node (ref "D58") (pin "1") (pinfunction "R+_1") (pintype "power_in"))
      (node (ref "D58") (pin "2") (pinfunction "G+_2") (pintype "power_in"))
      (node (ref "D58") (pin "3") (pinfunction "B+_3") (pintype "power_in"))
      (node (ref "D59") (pin "1") (pinfunction "R+_1") (pintype "power_in"))
      (node (ref "D59") (pin "2") (pinfunction "G+_2") (pintype "power_in"))
      (node (ref "D59") (pin "3") (pinfunction "B+_3") (pintype "power_in"))
      (node (ref "D60") (pin "1") (pinfunction "R+_1") (pintype "power_in"))
      (node (ref "D60") (pin "2") (pinfunction "G+_2") (pintype "power_in"))
      (node (ref "D60") (pin "3") (pinfunction "B+_3") (pintype "power_in"))
      (node (ref "D61") (pin "1") (pinfunction "R+_1") (pintype "power_in"))
      (node (ref "D61") (pin "2") (pinfunction "G+_2") (pintype "power_in"))
      (node (ref "D61") (pin "3") (pinfunction "B+_3") (pintype "power_in"))
      (node (ref "D62") (pin "1") (pinfunction "R+_1") (pintype "power_in"))
      (node (ref "D62") (pin "2") (pinfunction "G+_2") (pintype "power_in"))
      (node (ref "D62") (pin "3") (pinfunction "B+_3") (pintype "power_in"))
      (node (ref "D63") (pin "1") (pinfunction "R+_1") (pintype "power_in"))
      (node (ref "D63") (pin "2") (pinfunction "G+_2") (pintype "power_in"))
      (node (ref "D63") (pin "3") (pinfunction "B+_3") (pintype "power_in"))
      (node (ref "D64") (pin "1") (pinfunction "R+_1") (pintype "power_in"))
      (node (ref "D64") (pin "2") (pinfunction "G+_2") (pintype "power_in"))
      (node (ref "D64") (pin "3") (pinfunction "B+_3") (pintype "power_in"))
      (node (ref "Q8") (pin "4") (pinfunction "P_DRAIN_4") (pintype "passive"))
    )
    (net (code "38") (name "Net-(Q1-N_DRAIN)") (class "Default")
      (node (ref "Q1") (pin "3") (pinfunction "P_GATE_3") (pintype "passive"))
      (node (ref "Q1") (pin "6") (pinfunction "N_DRAIN_6") (pintype "passive"))
      (node (ref "R1") (pin "1") (pinfunction "1_1") (pintype "passive"))
    )
    (net (code "39") (name "Net-(Q2-N_DRAIN)") (class "Default")
      (node (ref "Q2") (pin "3") (pinfunction "P_GATE_3") (pintype "passive"))
      (node (ref "Q2") (pin "6") (pinfunction "N_DRAIN_6") (pintype "passive"))
      (node (ref "R2") (pin "1") (pinfunction "1_1") (pintype "passive"))
    )
    (net (code "40") (name "Net-(Q3-N_DRAIN)") (class "Default")
      (node (ref "Q3") (pin "3") (pinfunction "P_GATE_3") (pintype "passive"))
      (node (ref "Q3") (pin "6") (pinfunction "N_DRAIN_6") (pintype "passive"))
      (node (ref "R3") (pin "1") (pinfunction "1_1") (pintype "passive"))
    )
    (net (code "41") (name "Net-(Q4-N_DRAIN)") (class "Default")
      (node (ref "Q4") (pin "3") (pinfunction "P_GATE_3") (pintype "passive"))
      (node (ref "Q4") (pin "6") (pinfunction "N_DRAIN_6") (pintype "passive"))
      (node (ref "R4") (pin "1") (pinfunction "1_1") (pintype "passive"))
    )
    (net (code "42") (name "Net-(Q5-N_DRAIN)") (class "Default")
      (node (ref "Q5") (pin "3") (pinfunction "P_GATE_3") (pintype "passive"))
      (node (ref "Q5") (pin "6") (pinfunction "N_DRAIN_6") (pintype "passive"))
      (node (ref "R5") (pin "1") (pinfunction "1_1") (pintype "passive"))
    )
    (net (code "43") (name "Net-(Q6-N_DRAIN)") (class "Default")
      (node (ref "Q6") (pin "3") (pinfunction "P_GATE_3") (pintype "passive"))
      (node (ref "Q6") (pin "6") (pinfunction "N_DRAIN_6") (pintype "passive"))
      (node (ref "R6") (pin "1") (pinfunction "1_1") (pintype "passive"))
    )
    (net (code "44") (name "Net-(Q7-N_DRAIN)") (class "Default")
      (node (ref "Q7") (pin "3") (pinfunction "P_GATE_3") (pintype "passive"))
      (node (ref "Q7") (pin "6") (pinfunction "N_DRAIN_6") (pintype "passive"))
      (node (ref "R7") (pin "1") (pinfunction "1_1") (pintype "passive"))
    )
    (net (code "45") (name "Net-(Q8-N_DRAIN)") (class "Default")
      (node (ref "Q8") (pin "3") (pinfunction "P_GATE_3") (pintype "passive"))
      (node (ref "Q8") (pin "6") (pinfunction "N_DRAIN_6") (pintype "passive"))
      (node (ref "R8") (pin "1") (pinfunction "1_1") (pintype "passive"))
    )
    (net (code "46") (name "VCC") (class "Default")
      (node (ref "Q1") (pin "2") (pinfunction "P_SOURCE_2") (pintype "passive"))
      (node (ref "Q2") (pin "2") (pinfunction "P_SOURCE_2") (pintype "passive"))
      (node (ref "Q3") (pin "2") (pinfunction "P_SOURCE_2") (pintype "passive"))
      (node (ref "Q4") (pin "2") (pinfunction "P_SOURCE_2") (pintype "passive"))
      (node (ref "Q5") (pin "2") (pinfunction "P_SOURCE_2") (pintype "passive"))
      (node (ref "Q6") (pin "2") (pinfunction "P_SOURCE_2") (pintype "passive"))
      (node (ref "Q7") (pin "2") (pinfunction "P_SOURCE_2") (pintype "passive"))
      (node (ref "Q8") (pin "2") (pinfunction "P_SOURCE_2") (pintype "passive"))
      (node (ref "R1") (pin "2") (pinfunction "2_2") (pintype "passive"))
      (node (ref "R2") (pin "2") (pinfunction "2_2") (pintype "passive"))
      (node (ref "R3") (pin "2") (pinfunction "2_2") (pintype "passive"))
      (node (ref "R4") (pin "2") (pinfunction "2_2") (pintype "passive"))
      (node (ref "R5") (pin "2") (pinfunction "2_2") (pintype "passive"))
      (node (ref "R6") (pin "2") (pinfunction "2_2") (pintype "passive"))
      (node (ref "R7") (pin "2") (pinfunction "2_2") (pintype "passive"))
      (node (ref "R8") (pin "2") (pinfunction "2_2") (pintype "passive"))
    )
    (net (code "47") (name "unconnected-(Q1-N_GATE-Pad1)") (class "Default")
      (node (ref "Q1") (pin "1") (pinfunction "N_GATE_1") (pintype "passive"))
    )
    (net (code "48") (name "unconnected-(Q2-N_GATE-Pad1)") (class "Default")
      (node (ref "Q2") (pin "1") (pinfunction "N_GATE_1") (pintype "passive"))
    )
    (net (code "49") (name "unconnected-(Q3-N_GATE-Pad1)") (class "Default")
      (node (ref "Q3") (pin "1") (pinfunction "N_GATE_1") (pintype "passive"))
    )
    (net (code "50") (name "unconnected-(Q4-N_GATE-Pad1)") (class "Default")
      (node (ref "Q4") (pin "1") (pinfunction "N_GATE_1") (pintype "passive"))
    )
    (net (code "51") (name "unconnected-(Q5-N_GATE-Pad1)") (class "Default")
      (node (ref "Q5") (pin "1") (pinfunction "N_GATE_1") (pintype "passive"))
    )
    (net (code "52") (name "unconnected-(Q6-N_GATE-Pad1)") (class "Default")
      (node (ref "Q6") (pin "1") (pinfunction "N_GATE_1") (pintype "passive"))
    )
    (net (code "53") (name "unconnected-(Q7-N_GATE-Pad1)") (class "Default")
      (node (ref "Q7") (pin "1") (pinfunction "N_GATE_1") (pintype "passive"))
    )
    (net (code "54") (name "unconnected-(Q8-N_GATE-Pad1)") (class "Default")
      (node (ref "Q8") (pin "1") (pinfunction "N_GATE_1") (pintype "passive"))
    )
  )
)
